# schema4.net
KiCad netlist of a schematic drawn in Altium Designer
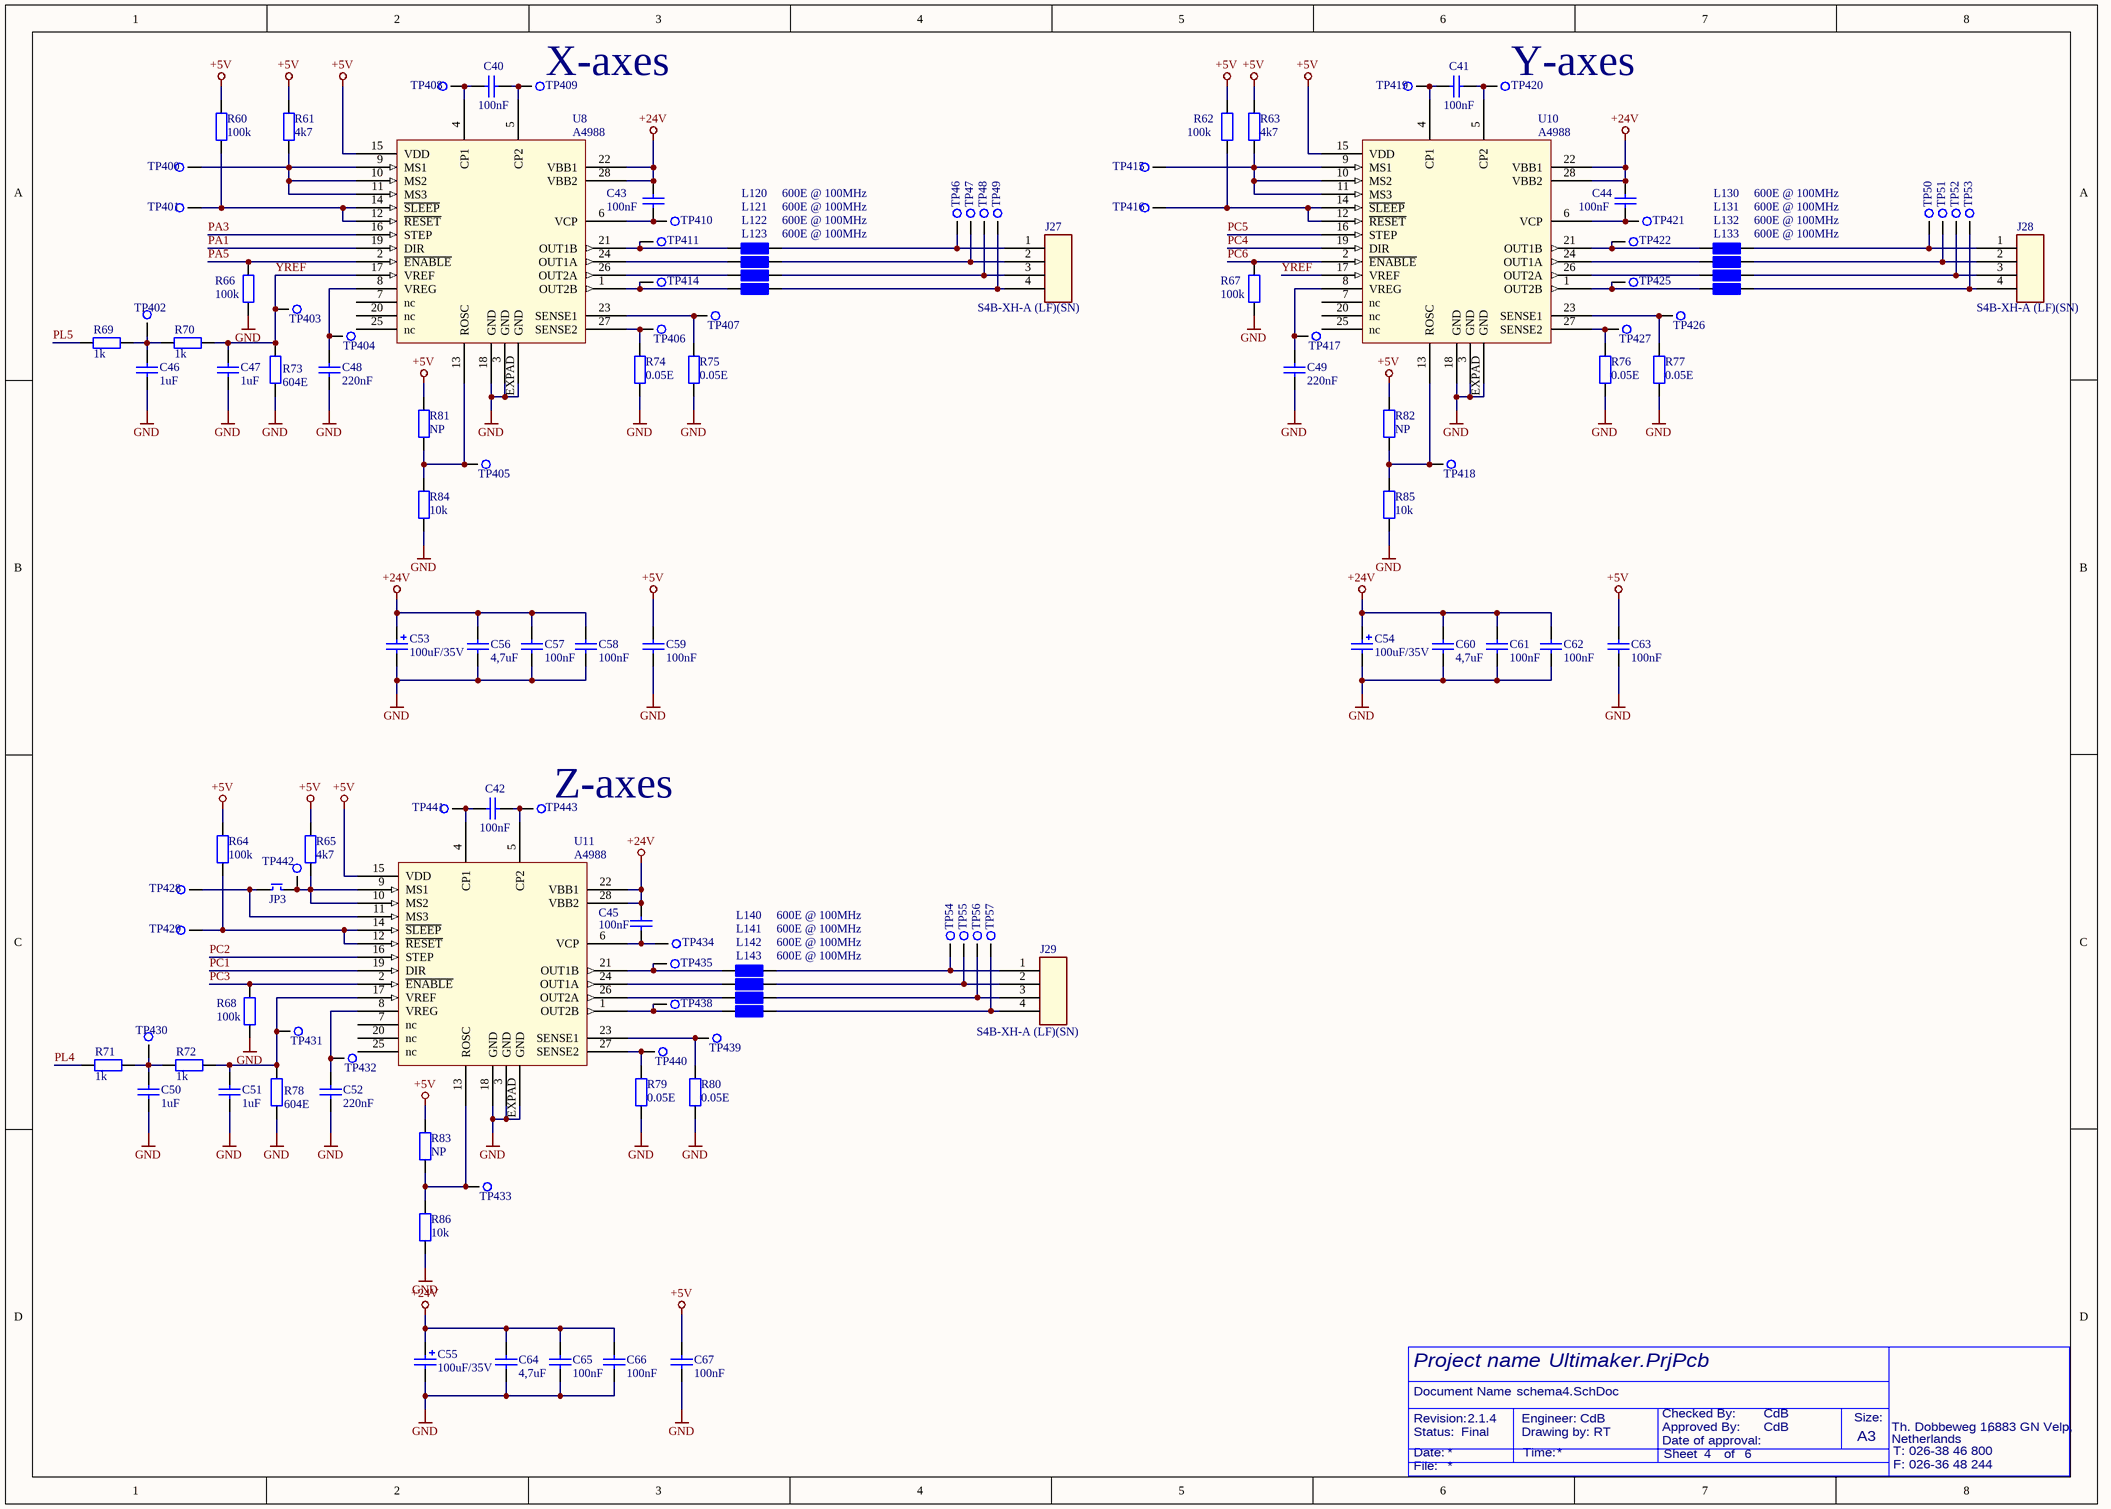
[diagram p0: schema4.SchDoc]

(export (version "E")
  (design (tool "Eeschema 10.0.6"))
  (components
    (comp (ref "C40")
      (value "100nF")
      (footprint "C0603")
      (description "RO X7R 100nF 10% 50V 0603")
      (libsource (lib "Database_Faber") (part "Capacitor"))
    )
    (comp (ref "C41")
      (value "100nF")
      (footprint "C0603")
      (description "RO X7R 100nF 10% 50V 0603")
      (libsource (lib "Database_Faber") (part "Capacitor"))
    )
    (comp (ref "C42")
      (value "100nF")
      (footprint "C0603")
      (description "RO X7R 100nF 10% 50V 0603")
      (libsource (lib "Database_Faber") (part "Capacitor"))
    )
    (comp (ref "C43")
      (value "100nF")
      (footprint "C0603")
      (description "RO X7R 100nF 10% 50V 0603")
      (libsource (lib "Database_Faber") (part "Capacitor"))
    )
    (comp (ref "C44")
      (value "100nF")
      (footprint "C0603")
      (description "RO X7R 100nF 10% 50V 0603")
      (libsource (lib "Database_Faber") (part "Capacitor"))
    )
    (comp (ref "C45")
      (value "100nF")
      (footprint "C0603")
      (description "RO X7R 100nF 10% 50V 0603")
      (libsource (lib "Database_Faber") (part "Capacitor"))
    )
    (comp (ref "C46")
      (value "1uF")
      (footprint "C0603")
      (description "RO X5R 1uF 10% 10V 0603")
      (libsource (lib "Database_Faber") (part "Capacitor"))
    )
    (comp (ref "C47")
      (value "1uF")
      (footprint "C0603")
      (description "RO X5R 1uF 10% 10V 0603")
      (libsource (lib "Database_Faber") (part "Capacitor"))
    )
    (comp (ref "C48")
      (value "220nF")
      (footprint "C0603")
      (description "RO X7R 220nF 10% 25V  0603")
      (libsource (lib "Database_Faber") (part "Capacitor"))
    )
    (comp (ref "C49")
      (value "220nF")
      (footprint "C0603")
      (description "RO X7R 220nF 10% 25V  0603")
      (libsource (lib "Database_Faber") (part "Capacitor"))
    )
    (comp (ref "C50")
      (value "1uF")
      (footprint "C0603")
      (description "RO X5R 1uF 10% 10V 0603")
      (libsource (lib "Database_Faber") (part "Capacitor"))
    )
    (comp (ref "C51")
      (value "1uF")
      (footprint "C0603")
      (description "RO X5R 1uF 10% 10V 0603")
      (libsource (lib "Database_Faber") (part "Capacitor"))
    )
    (comp (ref "C52")
      (value "220nF")
      (footprint "C0603")
      (description "RO X7R 220nF 10% 25V  0603")
      (libsource (lib "Database_Faber") (part "Capacitor"))
    )
    (comp (ref "C53")
      (value "100uF/35V")
      (footprint "ELCO Case D")
      (description "RO ELCO 100uF 20% 35V CASE-D EEEFP PAN")
      (libsource (lib "Database_Faber") (part "Capacitor Polarity"))
    )
    (comp (ref "C54")
      (value "100uF/35V")
      (footprint "ELCO Case D")
      (description "RO ELCO 100uF 20% 35V CASE-D EEEFP PAN")
      (libsource (lib "Database_Faber") (part "Capacitor Polarity"))
    )
    (comp (ref "C55")
      (value "100uF/35V")
      (footprint "ELCO Case D")
      (description "RO ELCO 100uF 20% 35V CASE-D EEEFP PAN")
      (libsource (lib "Database_Faber") (part "Capacitor Polarity"))
    )
    (comp (ref "C56")
      (value "4,7uF")
      (footprint "C1206")
      (description "RO X7R 4,7uF 10% 50V 1206")
      (libsource (lib "Database_Faber") (part "Capacitor"))
    )
    (comp (ref "C57")
      (value "100nF")
      (footprint "C0603")
      (description "RO X7R 100nF 10% 50V 0603")
      (libsource (lib "Database_Faber") (part "Capacitor"))
    )
    (comp (ref "C58")
      (value "100nF")
      (footprint "C0603")
      (description "RO X7R 100nF 10% 50V 0603")
      (libsource (lib "Database_Faber") (part "Capacitor"))
    )
    (comp (ref "C59")
      (value "100nF")
      (footprint "C0603")
      (description "RO X7R 100nF 10% 50V 0603")
      (libsource (lib "Database_Faber") (part "Capacitor"))
    )
    (comp (ref "C60")
      (value "4,7uF")
      (footprint "C1206")
      (description "RO X7R 4,7uF 10% 50V 1206")
      (libsource (lib "Database_Faber") (part "Capacitor"))
    )
    (comp (ref "C61")
      (value "100nF")
      (footprint "C0603")
      (description "RO X7R 100nF 10% 50V 0603")
      (libsource (lib "Database_Faber") (part "Capacitor"))
    )
    (comp (ref "C62")
      (value "100nF")
      (footprint "C0603")
      (description "RO X7R 100nF 10% 50V 0603")
      (libsource (lib "Database_Faber") (part "Capacitor"))
    )
    (comp (ref "C63")
      (value "100nF")
      (footprint "C0603")
      (description "RO X7R 100nF 10% 50V 0603")
      (libsource (lib "Database_Faber") (part "Capacitor"))
    )
    (comp (ref "C64")
      (value "4,7uF")
      (footprint "C1206")
      (description "RO X7R 4,7uF 10% 50V 1206")
      (libsource (lib "Database_Faber") (part "Capacitor"))
    )
    (comp (ref "C65")
      (value "100nF")
      (footprint "C0603")
      (description "RO X7R 100nF 10% 50V 0603")
      (libsource (lib "Database_Faber") (part "Capacitor"))
    )
    (comp (ref "C66")
      (value "100nF")
      (footprint "C0603")
      (description "RO X7R 100nF 10% 50V 0603")
      (libsource (lib "Database_Faber") (part "Capacitor"))
    )
    (comp (ref "C67")
      (value "100nF")
      (footprint "C0603")
      (description "RO X7R 100nF 10% 50V 0603")
      (libsource (lib "Database_Faber") (part "Capacitor"))
    )
    (comp (ref "J27")
      (value "S4B-XH-A (LF)(SN)")
      (footprint "S4B-XH-A (LF)(SN)")
      (description "RO CONN PR 4p HKS S4B-XH-A (LF)(SN) JST")
      (fields (field (name "MFG") "JST (JAPAN SOLDERLESS TERMINALS)"))
      (libsource (lib "Database_Faber") (part "HEADER 4"))
    )
    (comp (ref "J28")
      (value "S4B-XH-A (LF)(SN)")
      (footprint "S4B-XH-A (LF)(SN)")
      (description "RO CONN PR 4p HKS S4B-XH-A (LF)(SN) JST")
      (fields (field (name "MFG") "JST (JAPAN SOLDERLESS TERMINALS)"))
      (libsource (lib "Database_Faber") (part "HEADER 4"))
    )
    (comp (ref "J29")
      (value "S4B-XH-A (LF)(SN)")
      (footprint "S4B-XH-A (LF)(SN)")
      (description "RO CONN PR 4p HKS S4B-XH-A (LF)(SN) JST")
      (fields (field (name "MFG") "JST (JAPAN SOLDERLESS TERMINALS)"))
      (libsource (lib "Database_Faber") (part "HEADER 4"))
    )
    (comp (ref "JP3")
      (value "HEADER 2")
      (footprint "HEADER-1x2P-ST-2.54")
      (description "HEADER-1x2P-ST-2.54")
      (libsource (lib "Database_Faber") (part "JUMPER 2"))
    )
    (comp (ref "L120")
      (value "600E @ 100MHz")
      (footprint "R1206")
      (description "FERRIET 742792118 1206 Wurth Elektronik")
      (fields (field (name "MFG") "Wurth Elektronics"))
      (libsource (lib "Ultimaker") (part "Ferriet Bead 600E"))
    )
    (comp (ref "L121")
      (value "600E @ 100MHz")
      (footprint "R1206")
      (description "FERRIET 742792118 1206 Wurth Elektronik")
      (fields (field (name "MFG") "Wurth Elektronics"))
      (libsource (lib "Ultimaker") (part "Ferriet Bead 600E"))
    )
    (comp (ref "L122")
      (value "600E @ 100MHz")
      (footprint "R1206")
      (description "FERRIET 742792118 1206 Wurth Elektronik")
      (fields (field (name "MFG") "Wurth Elektronics"))
      (libsource (lib "Ultimaker") (part "Ferriet Bead 600E"))
    )
    (comp (ref "L123")
      (value "600E @ 100MHz")
      (footprint "R1206")
      (description "FERRIET 742792118 1206 Wurth Elektronik")
      (fields (field (name "MFG") "Wurth Elektronics"))
      (libsource (lib "Ultimaker") (part "Ferriet Bead 600E"))
    )
    (comp (ref "L130")
      (value "600E @ 100MHz")
      (footprint "R1206")
      (description "FERRIET 742792118 1206 Wurth Elektronik")
      (fields (field (name "MFG") "Wurth Elektronics"))
      (libsource (lib "Ultimaker") (part "Ferriet Bead 600E"))
    )
    (comp (ref "L131")
      (value "600E @ 100MHz")
      (footprint "R1206")
      (description "FERRIET 742792118 1206 Wurth Elektronik")
      (fields (field (name "MFG") "Wurth Elektronics"))
      (libsource (lib "Ultimaker") (part "Ferriet Bead 600E"))
    )
    (comp (ref "L132")
      (value "600E @ 100MHz")
      (footprint "R1206")
      (description "FERRIET 742792118 1206 Wurth Elektronik")
      (fields (field (name "MFG") "Wurth Elektronics"))
      (libsource (lib "Ultimaker") (part "Ferriet Bead 600E"))
    )
    (comp (ref "L133")
      (value "600E @ 100MHz")
      (footprint "R1206")
      (description "FERRIET 742792118 1206 Wurth Elektronik")
      (fields (field (name "MFG") "Wurth Elektronics"))
      (libsource (lib "Ultimaker") (part "Ferriet Bead 600E"))
    )
    (comp (ref "L140")
      (value "600E @ 100MHz")
      (footprint "R1206")
      (description "FERRIET 742792118 1206 Wurth Elektronik")
      (fields (field (name "MFG") "Wurth Elektronics"))
      (libsource (lib "Ultimaker") (part "Ferriet Bead 600E"))
    )
    (comp (ref "L141")
      (value "600E @ 100MHz")
      (footprint "R1206")
      (description "FERRIET 742792118 1206 Wurth Elektronik")
      (fields (field (name "MFG") "Wurth Elektronics"))
      (libsource (lib "Ultimaker") (part "Ferriet Bead 600E"))
    )
    (comp (ref "L142")
      (value "600E @ 100MHz")
      (footprint "R1206")
      (description "FERRIET 742792118 1206 Wurth Elektronik")
      (fields (field (name "MFG") "Wurth Elektronics"))
      (libsource (lib "Ultimaker") (part "Ferriet Bead 600E"))
    )
    (comp (ref "L143")
      (value "600E @ 100MHz")
      (footprint "R1206")
      (description "FERRIET 742792118 1206 Wurth Elektronik")
      (fields (field (name "MFG") "Wurth Elektronics"))
      (libsource (lib "Ultimaker") (part "Ferriet Bead 600E"))
    )
    (comp (ref "R60")
      (value "100k")
      (footprint "R0603")
      (description "RO RES 100k0 1% 0,063W  0603")
      (libsource (lib "Database_Faber") (part "Resistor"))
    )
    (comp (ref "R61")
      (value "4k7")
      (footprint "R0603")
      (description "RO RES 4k70 1% 0,063W  0603")
      (libsource (lib "Database_Faber") (part "Resistor"))
    )
    (comp (ref "R62")
      (value "100k")
      (footprint "R0603")
      (description "RO RES 100k0 1% 0,063W  0603")
      (libsource (lib "Database_Faber") (part "Resistor"))
    )
    (comp (ref "R63")
      (value "4k7")
      (footprint "R0603")
      (description "RO RES 4k70 1% 0,063W  0603")
      (libsource (lib "Database_Faber") (part "Resistor"))
    )
    (comp (ref "R64")
      (value "100k")
      (footprint "R0603")
      (description "RO RES 100k0 1% 0,063W  0603")
      (libsource (lib "Database_Faber") (part "Resistor"))
    )
    (comp (ref "R65")
      (value "4k7")
      (footprint "R0603")
      (description "RO RES 4k70 1% 0,063W  0603")
      (libsource (lib "Database_Faber") (part "Resistor"))
    )
    (comp (ref "R66")
      (value "100k")
      (footprint "R0603")
      (description "RO RES 100k0 1% 0,063W  0603")
      (libsource (lib "") (part "Resistor_1"))
    )
    (comp (ref "R67")
      (value "100k")
      (footprint "R0603")
      (description "RO RES 100k0 1% 0,063W  0603")
      (libsource (lib "") (part "Resistor_1"))
    )
    (comp (ref "R68")
      (value "100k")
      (footprint "R0603")
      (description "RO RES 100k0 1% 0,063W  0603")
      (libsource (lib "") (part "Resistor_1"))
    )
    (comp (ref "R69")
      (value "1k")
      (footprint "R0603")
      (description "RO RES 1k0 1% 0,1W  0603")
      (libsource (lib "") (part "Resistor_2"))
    )
    (comp (ref "R70")
      (value "1k")
      (footprint "R0603")
      (description "RO RES 1k0 1% 0,1W  0603")
      (libsource (lib "") (part "Resistor_2"))
    )
    (comp (ref "R71")
      (value "1k")
      (footprint "R0603")
      (description "RO RES 1k0 1% 0,1W  0603")
      (libsource (lib "") (part "Resistor_2"))
    )
    (comp (ref "R72")
      (value "1k")
      (footprint "R0603")
      (description "RO RES 1k0 1% 0,1W  0603")
      (libsource (lib "") (part "Resistor_2"))
    )
    (comp (ref "R73")
      (value "604E")
      (footprint "R0603")
      (description "RO RES 604E 1% 0,063W 0603")
      (fields (field (name "MFG") "VISHAY DRALORIC"))
      (libsource (lib "Database_Faber") (part "Resistor"))
    )
    (comp (ref "R74")
      (value "0.05E")
      (footprint "R0805")
      (description "RO RES 0E05 1% 0,125W 0805")
      (fields (field (name "MFG") "BOURNS"))
      (libsource (lib "Database_Faber") (part "Resistor"))
    )
    (comp (ref "R75")
      (value "0.05E")
      (footprint "R0805")
      (description "RO RES 0E05 1% 0,125W 0805")
      (fields (field (name "MFG") "BOURNS"))
      (libsource (lib "Database_Faber") (part "Resistor"))
    )
    (comp (ref "R76")
      (value "0.05E")
      (footprint "R0805")
      (description "RO RES 0E05 1% 0,125W 0805")
      (fields (field (name "MFG") "BOURNS"))
      (libsource (lib "Database_Faber") (part "Resistor"))
    )
    (comp (ref "R77")
      (value "0.05E")
      (footprint "R0805")
      (description "RO RES 0E05 1% 0,125W 0805")
      (fields (field (name "MFG") "BOURNS"))
      (libsource (lib "Database_Faber") (part "Resistor"))
    )
    (comp (ref "R78")
      (value "604E")
      (footprint "R0603")
      (description "RO RES 604E 1% 0,063W 0603")
      (fields (field (name "MFG") "VISHAY DRALORIC"))
      (libsource (lib "Database_Faber") (part "Resistor"))
    )
    (comp (ref "R79")
      (value "0.05E")
      (footprint "R0805")
      (description "RO RES 0E05 1% 0,125W 0805")
      (fields (field (name "MFG") "BOURNS"))
      (libsource (lib "Database_Faber") (part "Resistor"))
    )
    (comp (ref "R80")
      (value "0.05E")
      (footprint "R0805")
      (description "RO RES 0E05 1% 0,125W 0805")
      (fields (field (name "MFG") "BOURNS"))
      (libsource (lib "Database_Faber") (part "Resistor"))
    )
    (comp (ref "R81") (value "NP") (footprint "R0603") (libsource (lib "Database_Faber") (part "Resistor")))
    (comp (ref "R82") (value "NP") (footprint "R0603") (libsource (lib "Database_Faber") (part "Resistor")))
    (comp (ref "R83") (value "NP") (footprint "R0603") (libsource (lib "Database_Faber") (part "Resistor")))
    (comp (ref "R84")
      (value "10k")
      (footprint "R0603")
      (description "RO RES 10k0 1% 0,063W  0603")
      (libsource (lib "Database_Faber") (part "Resistor"))
    )
    (comp (ref "R85")
      (value "10k")
      (footprint "R0603")
      (description "RO RES 10k0 1% 0,063W  0603")
      (libsource (lib "Database_Faber") (part "Resistor"))
    )
    (comp (ref "R86")
      (value "10k")
      (footprint "R0603")
      (description "RO RES 10k0 1% 0,063W  0603")
      (libsource (lib "Database_Faber") (part "Resistor"))
    )
    (comp (ref "TP46")
      (value "Testpoint")
      (footprint "Testpoint")
      (libsource (lib "Database_Faber") (part "Testpoint"))
    )
    (comp (ref "TP47")
      (value "Testpoint")
      (footprint "Testpoint")
      (libsource (lib "Database_Faber") (part "Testpoint"))
    )
    (comp (ref "TP48")
      (value "Testpoint")
      (footprint "Testpoint")
      (libsource (lib "Database_Faber") (part "Testpoint"))
    )
    (comp (ref "TP49")
      (value "Testpoint")
      (footprint "Testpoint")
      (libsource (lib "Database_Faber") (part "Testpoint"))
    )
    (comp (ref "TP50")
      (value "Testpoint")
      (footprint "Testpoint")
      (libsource (lib "Database_Faber") (part "Testpoint"))
    )
    (comp (ref "TP51")
      (value "Testpoint")
      (footprint "Testpoint")
      (libsource (lib "Database_Faber") (part "Testpoint"))
    )
    (comp (ref "TP52")
      (value "Testpoint")
      (footprint "Testpoint")
      (libsource (lib "Database_Faber") (part "Testpoint"))
    )
    (comp (ref "TP53")
      (value "Testpoint")
      (footprint "Testpoint")
      (libsource (lib "Database_Faber") (part "Testpoint"))
    )
    (comp (ref "TP54")
      (value "Testpoint")
      (footprint "Testpoint")
      (libsource (lib "Database_Faber") (part "Testpoint"))
    )
    (comp (ref "TP55")
      (value "Testpoint")
      (footprint "Testpoint")
      (libsource (lib "Database_Faber") (part "Testpoint"))
    )
    (comp (ref "TP56")
      (value "Testpoint")
      (footprint "Testpoint")
      (libsource (lib "Database_Faber") (part "Testpoint"))
    )
    (comp (ref "TP57")
      (value "Testpoint")
      (footprint "Testpoint")
      (libsource (lib "Database_Faber") (part "Testpoint"))
    )
    (comp (ref "TP400")
      (value "Testpoint 1mm")
      (footprint "Testpoint 1mm")
      (libsource (lib "Ultimaker") (part "Testpoint 1mm"))
    )
    (comp (ref "TP401")
      (value "Testpoint 1mm")
      (footprint "Testpoint 1mm")
      (libsource (lib "Ultimaker") (part "Testpoint 1mm"))
    )
    (comp (ref "TP402")
      (value "Testpoint 1mm")
      (footprint "Testpoint 1mm")
      (libsource (lib "Ultimaker") (part "Testpoint 1mm"))
    )
    (comp (ref "TP403")
      (value "Testpoint 1mm")
      (footprint "Testpoint 1mm")
      (libsource (lib "Ultimaker") (part "Testpoint 1mm"))
    )
    (comp (ref "TP404")
      (value "Testpoint 1mm")
      (footprint "Testpoint 1mm")
      (libsource (lib "Ultimaker") (part "Testpoint 1mm"))
    )
    (comp (ref "TP405")
      (value "Testpoint 1mm")
      (footprint "Testpoint 1mm")
      (libsource (lib "Ultimaker") (part "Testpoint 1mm"))
    )
    (comp (ref "TP406")
      (value "Testpoint 1mm")
      (footprint "Testpoint 1mm")
      (libsource (lib "Ultimaker") (part "Testpoint 1mm"))
    )
    (comp (ref "TP407")
      (value "Testpoint 1mm")
      (footprint "Testpoint 1mm")
      (libsource (lib "Ultimaker") (part "Testpoint 1mm"))
    )
    (comp (ref "TP408")
      (value "Testpoint 1mm")
      (footprint "Testpoint 1mm")
      (libsource (lib "Ultimaker") (part "Testpoint 1mm"))
    )
    (comp (ref "TP409")
      (value "Testpoint 1mm")
      (footprint "Testpoint 1mm")
      (libsource (lib "Ultimaker") (part "Testpoint 1mm"))
    )
    (comp (ref "TP410")
      (value "Testpoint 1mm")
      (footprint "Testpoint 1mm")
      (libsource (lib "Ultimaker") (part "Testpoint 1mm"))
    )
    (comp (ref "TP411")
      (value "Testpoint 1mm")
      (footprint "Testpoint 1mm")
      (libsource (lib "Ultimaker") (part "Testpoint 1mm"))
    )
    (comp (ref "TP414")
      (value "Testpoint 1mm")
      (footprint "Testpoint 1mm")
      (libsource (lib "Ultimaker") (part "Testpoint 1mm"))
    )
    (comp (ref "TP415")
      (value "Testpoint 1mm")
      (footprint "Testpoint 1mm")
      (libsource (lib "Ultimaker") (part "Testpoint 1mm"))
    )
    (comp (ref "TP416")
      (value "Testpoint 1mm")
      (footprint "Testpoint 1mm")
      (libsource (lib "Ultimaker") (part "Testpoint 1mm"))
    )
    (comp (ref "TP417")
      (value "Testpoint 1mm")
      (footprint "Testpoint 1mm")
      (libsource (lib "Ultimaker") (part "Testpoint 1mm"))
    )
    (comp (ref "TP418")
      (value "Testpoint 1mm")
      (footprint "Testpoint 1mm")
      (libsource (lib "Ultimaker") (part "Testpoint 1mm"))
    )
    (comp (ref "TP419")
      (value "Testpoint 1mm")
      (footprint "Testpoint 1mm")
      (libsource (lib "Ultimaker") (part "Testpoint 1mm"))
    )
    (comp (ref "TP420")
      (value "Testpoint 1mm")
      (footprint "Testpoint 1mm")
      (libsource (lib "Ultimaker") (part "Testpoint 1mm"))
    )
    (comp (ref "TP421")
      (value "Testpoint 1mm")
      (footprint "Testpoint 1mm")
      (libsource (lib "Ultimaker") (part "Testpoint 1mm"))
    )
    (comp (ref "TP422")
      (value "Testpoint 1mm")
      (footprint "Testpoint 1mm")
      (libsource (lib "Ultimaker") (part "Testpoint 1mm"))
    )
    (comp (ref "TP425")
      (value "Testpoint 1mm")
      (footprint "Testpoint 1mm")
      (libsource (lib "Ultimaker") (part "Testpoint 1mm"))
    )
    (comp (ref "TP426")
      (value "Testpoint 1mm")
      (footprint "Testpoint 1mm")
      (libsource (lib "Ultimaker") (part "Testpoint 1mm"))
    )
    (comp (ref "TP427")
      (value "Testpoint 1mm")
      (footprint "Testpoint 1mm")
      (libsource (lib "Ultimaker") (part "Testpoint 1mm"))
    )
    (comp (ref "TP428")
      (value "Testpoint 1mm")
      (footprint "Testpoint 1mm")
      (libsource (lib "Ultimaker") (part "Testpoint 1mm"))
    )
    (comp (ref "TP429")
      (value "Testpoint 1mm")
      (footprint "Testpoint 1mm")
      (libsource (lib "Ultimaker") (part "Testpoint 1mm"))
    )
    (comp (ref "TP430")
      (value "Testpoint 1mm")
      (footprint "Testpoint 1mm")
      (libsource (lib "Ultimaker") (part "Testpoint 1mm"))
    )
    (comp (ref "TP431")
      (value "Testpoint 1mm")
      (footprint "Testpoint 1mm")
      (libsource (lib "Ultimaker") (part "Testpoint 1mm"))
    )
    (comp (ref "TP432")
      (value "Testpoint 1mm")
      (footprint "Testpoint 1mm")
      (libsource (lib "Ultimaker") (part "Testpoint 1mm"))
    )
    (comp (ref "TP433")
      (value "Testpoint 1mm")
      (footprint "Testpoint 1mm")
      (libsource (lib "Ultimaker") (part "Testpoint 1mm"))
    )
    (comp (ref "TP434")
      (value "Testpoint 1mm")
      (footprint "Testpoint 1mm")
      (libsource (lib "Ultimaker") (part "Testpoint 1mm"))
    )
    (comp (ref "TP435")
      (value "Testpoint 1mm")
      (footprint "Testpoint 1mm")
      (libsource (lib "Ultimaker") (part "Testpoint 1mm"))
    )
    (comp (ref "TP438")
      (value "Testpoint 1mm")
      (footprint "Testpoint 1mm")
      (libsource (lib "Ultimaker") (part "Testpoint 1mm"))
    )
    (comp (ref "TP439")
      (value "Testpoint 1mm")
      (footprint "Testpoint 1mm")
      (libsource (lib "Ultimaker") (part "Testpoint 1mm"))
    )
    (comp (ref "TP440")
      (value "Testpoint 1mm")
      (footprint "Testpoint 1mm")
      (libsource (lib "Ultimaker") (part "Testpoint 1mm"))
    )
    (comp (ref "TP441")
      (value "Testpoint 1mm")
      (footprint "Testpoint 1mm")
      (libsource (lib "Ultimaker") (part "Testpoint 1mm"))
    )
    (comp (ref "TP442")
      (value "Testpoint 1mm")
      (footprint "Testpoint 1mm")
      (libsource (lib "Ultimaker") (part "Testpoint 1mm"))
    )
    (comp (ref "TP443")
      (value "Testpoint 1mm")
      (footprint "Testpoint 1mm")
      (libsource (lib "Ultimaker") (part "Testpoint 1mm"))
    )
    (comp (ref "U8")
      (value "A4988")
      (footprint "QFN50P500X500X100-28-EX")
      (description "RO IC A4988 QFN-28 ALLEGRO")
      (fields (field (name "MFG") "Allegro"))
      (libsource (lib "Database_Faber") (part "A4988"))
    )
    (comp (ref "U10")
      (value "A4988")
      (footprint "QFN50P500X500X100-28-EX")
      (description "RO IC A4988 QFN-28 ALLEGRO")
      (fields (field (name "MFG") "Allegro"))
      (libsource (lib "Database_Faber") (part "A4988"))
    )
    (comp (ref "U11")
      (value "A4988")
      (footprint "QFN50P500X500X100-28-EX")
      (description "RO IC A4988 QFN-28 ALLEGRO")
      (fields (field (name "MFG") "Allegro"))
      (libsource (lib "Database_Faber") (part "A4988"))
    )
  )
  (nets
    (net (code "1") (name "+5V") (class "Default")
      (node (ref "C59") (pin "2") (pinfunction "2_2") (pintype "passive"))
      (node (ref "C63") (pin "2") (pinfunction "2_2") (pintype "passive"))
      (node (ref "C67") (pin "2") (pinfunction "2_2") (pintype "passive"))
      (node (ref "R60") (pin "2") (pinfunction "2_2") (pintype "passive"))
      (node (ref "R61") (pin "2") (pinfunction "2_2") (pintype "passive"))
      (node (ref "R62") (pin "2") (pinfunction "2_2") (pintype "passive"))
      (node (ref "R63") (pin "2") (pinfunction "2_2") (pintype "passive"))
      (node (ref "R64") (pin "2") (pinfunction "2_2") (pintype "passive"))
      (node (ref "R65") (pin "2") (pinfunction "2_2") (pintype "passive"))
      (node (ref "R81") (pin "2") (pinfunction "2_2") (pintype "passive"))
      (node (ref "R82") (pin "2") (pinfunction "2_2") (pintype "passive"))
      (node (ref "R83") (pin "2") (pinfunction "2_2") (pintype "passive"))
      (node (ref "U10") (pin "15") (pinfunction "VDD_15") (pintype "power_in"))
      (node (ref "U11") (pin "15") (pinfunction "VDD_15") (pintype "power_in"))
      (node (ref "U8") (pin "15") (pinfunction "VDD_15") (pintype "power_in"))
    )
    (net (code "2") (name "+24V") (class "Default")
      (node (ref "C43") (pin "2") (pinfunction "2_2") (pintype "passive"))
      (node (ref "C44") (pin "2") (pinfunction "2_2") (pintype "passive"))
      (node (ref "C45") (pin "2") (pinfunction "2_2") (pintype "passive"))
      (node (ref "C53") (pin "1") (pinfunction "1_1") (pintype "passive"))
      (node (ref "C54") (pin "1") (pinfunction "1_1") (pintype "passive"))
      (node (ref "C55") (pin "1") (pinfunction "1_1") (pintype "passive"))
      (node (ref "C56") (pin "2") (pinfunction "2_2") (pintype "passive"))
      (node (ref "C57") (pin "2") (pinfunction "2_2") (pintype "passive"))
      (node (ref "C58") (pin "2") (pinfunction "2_2") (pintype "passive"))
      (node (ref "C60") (pin "2") (pinfunction "2_2") (pintype "passive"))
      (node (ref "C61") (pin "2") (pinfunction "2_2") (pintype "passive"))
      (node (ref "C62") (pin "2") (pinfunction "2_2") (pintype "passive"))
      (node (ref "C64") (pin "2") (pinfunction "2_2") (pintype "passive"))
      (node (ref "C65") (pin "2") (pinfunction "2_2") (pintype "passive"))
      (node (ref "C66") (pin "2") (pinfunction "2_2") (pintype "passive"))
      (node (ref "U10") (pin "22") (pinfunction "VBB1_22") (pintype "power_in"))
      (node (ref "U10") (pin "28") (pinfunction "VBB2_28") (pintype "power_in"))
      (node (ref "U11") (pin "22") (pinfunction "VBB1_22") (pintype "power_in"))
      (node (ref "U11") (pin "28") (pinfunction "VBB2_28") (pintype "power_in"))
      (node (ref "U8") (pin "22") (pinfunction "VBB1_22") (pintype "power_in"))
      (node (ref "U8") (pin "28") (pinfunction "VBB2_28") (pintype "power_in"))
    )
    (net (code "3") (name "/PA1") (class "Default")
      (node (ref "U8") (pin "19") (pinfunction "DIR_19") (pintype "input"))
    )
    (net (code "4") (name "/PA3") (class "Default")
      (node (ref "U8") (pin "16") (pinfunction "STEP_16") (pintype "input"))
    )
    (net (code "5") (name "/PA5") (class "Default")
      (node (ref "R66") (pin "1") (pinfunction "1_1") (pintype "passive"))
      (node (ref "U8") (pin "2") (pinfunction "~{ENABLE}_2") (pintype "input"))
    )
    (net (code "6") (name "/PC1") (class "Default")
      (node (ref "U11") (pin "19") (pinfunction "DIR_19") (pintype "input"))
    )
    (net (code "7") (name "/PC2") (class "Default")
      (node (ref "U11") (pin "16") (pinfunction "STEP_16") (pintype "input"))
    )
    (net (code "8") (name "/PC3") (class "Default")
      (node (ref "R68") (pin "1") (pinfunction "1_1") (pintype "passive"))
      (node (ref "U11") (pin "2") (pinfunction "~{ENABLE}_2") (pintype "input"))
    )
    (net (code "9") (name "/PC4") (class "Default")
      (node (ref "U10") (pin "19") (pinfunction "DIR_19") (pintype "input"))
    )
    (net (code "10") (name "/PC5") (class "Default")
      (node (ref "U10") (pin "16") (pinfunction "STEP_16") (pintype "input"))
    )
    (net (code "11") (name "/PC6") (class "Default")
      (node (ref "R67") (pin "1") (pinfunction "1_1") (pintype "passive"))
      (node (ref "U10") (pin "2") (pinfunction "~{ENABLE}_2") (pintype "input"))
    )
    (net (code "12") (name "/PL4") (class "Default")
      (node (ref "R71") (pin "1") (pinfunction "1_1") (pintype "passive"))
    )
    (net (code "13") (name "/PL5") (class "Default")
      (node (ref "R69") (pin "1") (pinfunction "1_1") (pintype "passive"))
    )
    (net (code "14") (name "/YREF") (class "Default")
      (node (ref "C47") (pin "2") (pinfunction "2_2") (pintype "passive"))
      (node (ref "R70") (pin "2") (pinfunction "2_2") (pintype "passive"))
      (node (ref "R73") (pin "2") (pinfunction "2_2") (pintype "passive"))
      (node (ref "TP403") (pin "1") (pinfunction "1_1") (pintype "passive"))
      (node (ref "U10") (pin "17") (pinfunction "VREF_17") (pintype "input"))
      (node (ref "U8") (pin "17") (pinfunction "VREF_17") (pintype "input"))
    )
    (net (code "15") (name "GND") (class "Default")
      (node (ref "C46") (pin "1") (pinfunction "1_1") (pintype "passive"))
      (node (ref "C47") (pin "1") (pinfunction "1_1") (pintype "passive"))
      (node (ref "C48") (pin "1") (pinfunction "1_1") (pintype "passive"))
      (node (ref "C49") (pin "1") (pinfunction "1_1") (pintype "passive"))
      (node (ref "C50") (pin "1") (pinfunction "1_1") (pintype "passive"))
      (node (ref "C51") (pin "1") (pinfunction "1_1") (pintype "passive"))
      (node (ref "C52") (pin "1") (pinfunction "1_1") (pintype "passive"))
      (node (ref "C53") (pin "2") (pinfunction "2_2") (pintype "passive"))
      (node (ref "C54") (pin "2") (pinfunction "2_2") (pintype "passive"))
      (node (ref "C55") (pin "2") (pinfunction "2_2") (pintype "passive"))
      (node (ref "C56") (pin "1") (pinfunction "1_1") (pintype "passive"))
      (node (ref "C57") (pin "1") (pinfunction "1_1") (pintype "passive"))
      (node (ref "C58") (pin "1") (pinfunction "1_1") (pintype "passive"))
      (node (ref "C59") (pin "1") (pinfunction "1_1") (pintype "passive"))
      (node (ref "C60") (pin "1") (pinfunction "1_1") (pintype "passive"))
      (node (ref "C61") (pin "1") (pinfunction "1_1") (pintype "passive"))
      (node (ref "C62") (pin "1") (pinfunction "1_1") (pintype "passive"))
      (node (ref "C63") (pin "1") (pinfunction "1_1") (pintype "passive"))
      (node (ref "C64") (pin "1") (pinfunction "1_1") (pintype "passive"))
      (node (ref "C65") (pin "1") (pinfunction "1_1") (pintype "passive"))
      (node (ref "C66") (pin "1") (pinfunction "1_1") (pintype "passive"))
      (node (ref "C67") (pin "1") (pinfunction "1_1") (pintype "passive"))
      (node (ref "R66") (pin "2") (pinfunction "2_2") (pintype "passive"))
      (node (ref "R67") (pin "2") (pinfunction "2_2") (pintype "passive"))
      (node (ref "R68") (pin "2") (pinfunction "2_2") (pintype "passive"))
      (node (ref "R73") (pin "1") (pinfunction "1_1") (pintype "passive"))
      (node (ref "R74") (pin "1") (pinfunction "1_1") (pintype "passive"))
      (node (ref "R75") (pin "1") (pinfunction "1_1") (pintype "passive"))
      (node (ref "R76") (pin "1") (pinfunction "1_1") (pintype "passive"))
      (node (ref "R77") (pin "1") (pinfunction "1_1") (pintype "passive"))
      (node (ref "R78") (pin "1") (pinfunction "1_1") (pintype "passive"))
      (node (ref "R79") (pin "1") (pinfunction "1_1") (pintype "passive"))
      (node (ref "R80") (pin "1") (pinfunction "1_1") (pintype "passive"))
      (node (ref "R84") (pin "1") (pinfunction "1_1") (pintype "passive"))
      (node (ref "R85") (pin "1") (pinfunction "1_1") (pintype "passive"))
      (node (ref "R86") (pin "1") (pinfunction "1_1") (pintype "passive"))
      (node (ref "U10") (pin "18") (pinfunction "GND_18") (pintype "passive"))
      (node (ref "U10") (pin "3") (pinfunction "GND_3") (pintype "power_in"))
      (node (ref "U10") (pin "EXPAD") (pinfunction "GND_EXPAD") (pintype "power_in"))
      (node (ref "U11") (pin "18") (pinfunction "GND_18") (pintype "passive"))
      (node (ref "U11") (pin "3") (pinfunction "GND_3") (pintype "power_in"))
      (node (ref "U11") (pin "EXPAD") (pinfunction "GND_EXPAD") (pintype "power_in"))
      (node (ref "U8") (pin "18") (pinfunction "GND_18") (pintype "passive"))
      (node (ref "U8") (pin "3") (pinfunction "GND_3") (pintype "power_in"))
      (node (ref "U8") (pin "EXPAD") (pinfunction "GND_EXPAD") (pintype "power_in"))
    )
    (net (code "16") (name "Net-(C46-Pad2)") (class "Default")
      (node (ref "C46") (pin "2") (pinfunction "2_2") (pintype "passive"))
      (node (ref "R69") (pin "2") (pinfunction "2_2") (pintype "passive"))
      (node (ref "R70") (pin "1") (pinfunction "1_1") (pintype "passive"))
      (node (ref "TP402") (pin "1") (pinfunction "1_1") (pintype "passive"))
    )
    (net (code "17") (name "Net-(C50-Pad2)") (class "Default")
      (node (ref "C50") (pin "2") (pinfunction "2_2") (pintype "passive"))
      (node (ref "R71") (pin "2") (pinfunction "2_2") (pintype "passive"))
      (node (ref "R72") (pin "1") (pinfunction "1_1") (pintype "passive"))
      (node (ref "TP430") (pin "1") (pinfunction "1_1") (pintype "passive"))
    )
    (net (code "18") (name "Net-(J27-Pad1)") (class "Default")
      (node (ref "J27") (pin "1") (pinfunction "1_1") (pintype "passive"))
      (node (ref "L120") (pin "2") (pinfunction "2_2") (pintype "passive"))
      (node (ref "TP46") (pin "1") (pinfunction "1_1") (pintype "passive"))
    )
    (net (code "19") (name "Net-(J27-Pad2)") (class "Default")
      (node (ref "J27") (pin "2") (pinfunction "2_2") (pintype "passive"))
      (node (ref "L121") (pin "2") (pinfunction "2_2") (pintype "passive"))
      (node (ref "TP47") (pin "1") (pinfunction "1_1") (pintype "passive"))
    )
    (net (code "20") (name "Net-(J27-Pad3)") (class "Default")
      (node (ref "J27") (pin "3") (pinfunction "3_3") (pintype "passive"))
      (node (ref "L122") (pin "2") (pinfunction "2_2") (pintype "passive"))
      (node (ref "TP48") (pin "1") (pinfunction "1_1") (pintype "passive"))
    )
    (net (code "21") (name "Net-(J27-Pad4)") (class "Default")
      (node (ref "J27") (pin "4") (pinfunction "4_4") (pintype "passive"))
      (node (ref "L123") (pin "2") (pinfunction "2_2") (pintype "passive"))
      (node (ref "TP49") (pin "1") (pinfunction "1_1") (pintype "passive"))
    )
    (net (code "22") (name "Net-(J28-Pad1)") (class "Default")
      (node (ref "J28") (pin "1") (pinfunction "1_1") (pintype "passive"))
      (node (ref "L130") (pin "2") (pinfunction "2_2") (pintype "passive"))
      (node (ref "TP50") (pin "1") (pinfunction "1_1") (pintype "passive"))
    )
    (net (code "23") (name "Net-(J28-Pad2)") (class "Default")
      (node (ref "J28") (pin "2") (pinfunction "2_2") (pintype "passive"))
      (node (ref "L131") (pin "2") (pinfunction "2_2") (pintype "passive"))
      (node (ref "TP51") (pin "1") (pinfunction "1_1") (pintype "passive"))
    )
    (net (code "24") (name "Net-(J28-Pad3)") (class "Default")
      (node (ref "J28") (pin "3") (pinfunction "3_3") (pintype "passive"))
      (node (ref "L132") (pin "2") (pinfunction "2_2") (pintype "passive"))
      (node (ref "TP52") (pin "1") (pinfunction "1_1") (pintype "passive"))
    )
    (net (code "25") (name "Net-(J28-Pad4)") (class "Default")
      (node (ref "J28") (pin "4") (pinfunction "4_4") (pintype "passive"))
      (node (ref "L133") (pin "2") (pinfunction "2_2") (pintype "passive"))
      (node (ref "TP53") (pin "1") (pinfunction "1_1") (pintype "passive"))
    )
    (net (code "26") (name "Net-(J29-Pad1)") (class "Default")
      (node (ref "J29") (pin "1") (pinfunction "1_1") (pintype "passive"))
      (node (ref "L140") (pin "2") (pinfunction "2_2") (pintype "passive"))
      (node (ref "TP54") (pin "1") (pinfunction "1_1") (pintype "passive"))
    )
    (net (code "27") (name "Net-(J29-Pad2)") (class "Default")
      (node (ref "J29") (pin "2") (pinfunction "2_2") (pintype "passive"))
      (node (ref "L141") (pin "2") (pinfunction "2_2") (pintype "passive"))
      (node (ref "TP55") (pin "1") (pinfunction "1_1") (pintype "passive"))
    )
    (net (code "28") (name "Net-(J29-Pad3)") (class "Default")
      (node (ref "J29") (pin "3") (pinfunction "3_3") (pintype "passive"))
      (node (ref "L142") (pin "2") (pinfunction "2_2") (pintype "passive"))
      (node (ref "TP56") (pin "1") (pinfunction "1_1") (pintype "passive"))
    )
    (net (code "29") (name "Net-(J29-Pad4)") (class "Default")
      (node (ref "J29") (pin "4") (pinfunction "4_4") (pintype "passive"))
      (node (ref "L143") (pin "2") (pinfunction "2_2") (pintype "passive"))
      (node (ref "TP57") (pin "1") (pinfunction "1_1") (pintype "passive"))
    )
    (net (code "30") (name "Net-(U8-CP1)") (class "Default")
      (node (ref "C40") (pin "1") (pinfunction "1_1") (pintype "passive"))
      (node (ref "TP408") (pin "1") (pinfunction "1_1") (pintype "passive"))
      (node (ref "U8") (pin "4") (pinfunction "CP1_4") (pintype "passive"))
    )
    (net (code "31") (name "Net-(U8-CP2)") (class "Default")
      (node (ref "C40") (pin "2") (pinfunction "2_2") (pintype "passive"))
      (node (ref "TP409") (pin "1") (pinfunction "1_1") (pintype "passive"))
      (node (ref "U8") (pin "5") (pinfunction "CP2_5") (pintype "passive"))
    )
    (net (code "32") (name "Net-(U8-MS1)") (class "Default")
      (node (ref "R61") (pin "1") (pinfunction "1_1") (pintype "passive"))
      (node (ref "TP400") (pin "1") (pinfunction "1_1") (pintype "passive"))
      (node (ref "U8") (pin "10") (pinfunction "MS2_10") (pintype "input"))
      (node (ref "U8") (pin "11") (pinfunction "MS3_11") (pintype "input"))
      (node (ref "U8") (pin "9") (pinfunction "MS1_9") (pintype "input"))
    )
    (net (code "33") (name "Net-(U8-OUT1A)") (class "Default")
      (node (ref "L121") (pin "1") (pinfunction "1_1") (pintype "passive"))
      (node (ref "U8") (pin "24") (pinfunction "OUT1A_24") (pintype "output"))
    )
    (net (code "34") (name "Net-(U8-OUT1B)") (class "Default")
      (node (ref "L120") (pin "1") (pinfunction "1_1") (pintype "passive"))
      (node (ref "TP411") (pin "1") (pinfunction "1_1") (pintype "passive"))
      (node (ref "U8") (pin "21") (pinfunction "OUT1B_21") (pintype "output"))
    )
    (net (code "35") (name "Net-(U8-OUT2A)") (class "Default")
      (node (ref "L122") (pin "1") (pinfunction "1_1") (pintype "passive"))
      (node (ref "U8") (pin "26") (pinfunction "OUT2A_26") (pintype "output"))
    )
    (net (code "36") (name "Net-(U8-OUT2B)") (class "Default")
      (node (ref "L123") (pin "1") (pinfunction "1_1") (pintype "passive"))
      (node (ref "TP414") (pin "1") (pinfunction "1_1") (pintype "passive"))
      (node (ref "U8") (pin "1") (pinfunction "OUT2B_1") (pintype "output"))
    )
    (net (code "37") (name "Net-(U8-ROSC)") (class "Default")
      (node (ref "R81") (pin "1") (pinfunction "1_1") (pintype "passive"))
      (node (ref "R84") (pin "2") (pinfunction "2_2") (pintype "passive"))
      (node (ref "TP405") (pin "1") (pinfunction "1_1") (pintype "passive"))
      (node (ref "U8") (pin "13") (pinfunction "ROSC_13") (pintype "passive"))
    )
    (net (code "38") (name "Net-(U8-SENSE1)") (class "Default")
      (node (ref "R75") (pin "2") (pinfunction "2_2") (pintype "passive"))
      (node (ref "TP407") (pin "1") (pinfunction "1_1") (pintype "passive"))
      (node (ref "U8") (pin "23") (pinfunction "SENSE1_23") (pintype "passive"))
    )
    (net (code "39") (name "Net-(U8-SENSE2)") (class "Default")
      (node (ref "R74") (pin "2") (pinfunction "2_2") (pintype "passive"))
      (node (ref "TP406") (pin "1") (pinfunction "1_1") (pintype "passive"))
      (node (ref "U8") (pin "27") (pinfunction "SENSE2_27") (pintype "passive"))
    )
    (net (code "40") (name "Net-(U8-VCP)") (class "Default")
      (node (ref "C43") (pin "1") (pinfunction "1_1") (pintype "passive"))
      (node (ref "TP410") (pin "1") (pinfunction "1_1") (pintype "passive"))
      (node (ref "U8") (pin "6") (pinfunction "VCP_6") (pintype "passive"))
    )
    (net (code "41") (name "Net-(U8-VREG)") (class "Default")
      (node (ref "C48") (pin "2") (pinfunction "2_2") (pintype "passive"))
      (node (ref "TP404") (pin "1") (pinfunction "1_1") (pintype "passive"))
      (node (ref "U8") (pin "8") (pinfunction "VREG_8") (pintype "power_in"))
    )
    (net (code "42") (name "Net-(U8-~{RESET})") (class "Default")
      (node (ref "R60") (pin "1") (pinfunction "1_1") (pintype "passive"))
      (node (ref "TP401") (pin "1") (pinfunction "1_1") (pintype "passive"))
      (node (ref "U8") (pin "12") (pinfunction "~{RESET}_12") (pintype "input"))
      (node (ref "U8") (pin "14") (pinfunction "~{SLEEP}_14") (pintype "input"))
    )
    (net (code "43") (name "Net-(U10-CP1)") (class "Default")
      (node (ref "C41") (pin "1") (pinfunction "1_1") (pintype "passive"))
      (node (ref "TP419") (pin "1") (pinfunction "1_1") (pintype "passive"))
      (node (ref "U10") (pin "4") (pinfunction "CP1_4") (pintype "passive"))
    )
    (net (code "44") (name "Net-(U10-CP2)") (class "Default")
      (node (ref "C41") (pin "2") (pinfunction "2_2") (pintype "passive"))
      (node (ref "TP420") (pin "1") (pinfunction "1_1") (pintype "passive"))
      (node (ref "U10") (pin "5") (pinfunction "CP2_5") (pintype "passive"))
    )
    (net (code "45") (name "Net-(U10-MS1)") (class "Default")
      (node (ref "R63") (pin "1") (pinfunction "1_1") (pintype "passive"))
      (node (ref "TP415") (pin "1") (pinfunction "1_1") (pintype "passive"))
      (node (ref "U10") (pin "10") (pinfunction "MS2_10") (pintype "input"))
      (node (ref "U10") (pin "11") (pinfunction "MS3_11") (pintype "input"))
      (node (ref "U10") (pin "9") (pinfunction "MS1_9") (pintype "input"))
    )
    (net (code "46") (name "Net-(U10-OUT1A)") (class "Default")
      (node (ref "L131") (pin "1") (pinfunction "1_1") (pintype "passive"))
      (node (ref "U10") (pin "24") (pinfunction "OUT1A_24") (pintype "output"))
    )
    (net (code "47") (name "Net-(U10-OUT1B)") (class "Default")
      (node (ref "L130") (pin "1") (pinfunction "1_1") (pintype "passive"))
      (node (ref "TP422") (pin "1") (pinfunction "1_1") (pintype "passive"))
      (node (ref "U10") (pin "21") (pinfunction "OUT1B_21") (pintype "output"))
    )
    (net (code "48") (name "Net-(U10-OUT2A)") (class "Default")
      (node (ref "L132") (pin "1") (pinfunction "1_1") (pintype "passive"))
      (node (ref "U10") (pin "26") (pinfunction "OUT2A_26") (pintype "output"))
    )
    (net (code "49") (name "Net-(U10-OUT2B)") (class "Default")
      (node (ref "L133") (pin "1") (pinfunction "1_1") (pintype "passive"))
      (node (ref "TP425") (pin "1") (pinfunction "1_1") (pintype "passive"))
      (node (ref "U10") (pin "1") (pinfunction "OUT2B_1") (pintype "output"))
    )
    (net (code "50") (name "Net-(U10-ROSC)") (class "Default")
      (node (ref "R82") (pin "1") (pinfunction "1_1") (pintype "passive"))
      (node (ref "R85") (pin "2") (pinfunction "2_2") (pintype "passive"))
      (node (ref "TP418") (pin "1") (pinfunction "1_1") (pintype "passive"))
      (node (ref "U10") (pin "13") (pinfunction "ROSC_13") (pintype "passive"))
    )
    (net (code "51") (name "Net-(U10-SENSE1)") (class "Default")
      (node (ref "R77") (pin "2") (pinfunction "2_2") (pintype "passive"))
      (node (ref "TP426") (pin "1") (pinfunction "1_1") (pintype "passive"))
      (node (ref "U10") (pin "23") (pinfunction "SENSE1_23") (pintype "passive"))
    )
    (net (code "52") (name "Net-(U10-SENSE2)") (class "Default")
      (node (ref "R76") (pin "2") (pinfunction "2_2") (pintype "passive"))
      (node (ref "TP427") (pin "1") (pinfunction "1_1") (pintype "passive"))
      (node (ref "U10") (pin "27") (pinfunction "SENSE2_27") (pintype "passive"))
    )
    (net (code "53") (name "Net-(U10-VCP)") (class "Default")
      (node (ref "C44") (pin "1") (pinfunction "1_1") (pintype "passive"))
      (node (ref "TP421") (pin "1") (pinfunction "1_1") (pintype "passive"))
      (node (ref "U10") (pin "6") (pinfunction "VCP_6") (pintype "passive"))
    )
    (net (code "54") (name "Net-(U10-VREG)") (class "Default")
      (node (ref "C49") (pin "2") (pinfunction "2_2") (pintype "passive"))
      (node (ref "TP417") (pin "1") (pinfunction "1_1") (pintype "passive"))
      (node (ref "U10") (pin "8") (pinfunction "VREG_8") (pintype "power_in"))
    )
    (net (code "55") (name "Net-(U10-~{RESET})") (class "Default")
      (node (ref "R62") (pin "1") (pinfunction "1_1") (pintype "passive"))
      (node (ref "TP416") (pin "1") (pinfunction "1_1") (pintype "passive"))
      (node (ref "U10") (pin "12") (pinfunction "~{RESET}_12") (pintype "input"))
      (node (ref "U10") (pin "14") (pinfunction "~{SLEEP}_14") (pintype "input"))
    )
    (net (code "56") (name "Net-(U11-CP1)") (class "Default")
      (node (ref "C42") (pin "1") (pinfunction "1_1") (pintype "passive"))
      (node (ref "TP441") (pin "1") (pinfunction "1_1") (pintype "passive"))
      (node (ref "U11") (pin "4") (pinfunction "CP1_4") (pintype "passive"))
    )
    (net (code "57") (name "Net-(U11-CP2)") (class "Default")
      (node (ref "C42") (pin "2") (pinfunction "2_2") (pintype "passive"))
      (node (ref "TP443") (pin "1") (pinfunction "1_1") (pintype "passive"))
      (node (ref "U11") (pin "5") (pinfunction "CP2_5") (pintype "passive"))
    )
    (net (code "58") (name "Net-(U11-MS1)") (class "Default")
      (node (ref "JP3") (pin "2") (pinfunction "2_2") (pintype "passive"))
      (node (ref "R65") (pin "1") (pinfunction "1_1") (pintype "passive"))
      (node (ref "TP442") (pin "1") (pinfunction "1_1") (pintype "passive"))
      (node (ref "U11") (pin "10") (pinfunction "MS2_10") (pintype "input"))
      (node (ref "U11") (pin "9") (pinfunction "MS1_9") (pintype "input"))
    )
    (net (code "59") (name "Net-(U11-MS3)") (class "Default")
      (node (ref "JP3") (pin "1") (pinfunction "1_1") (pintype "passive"))
      (node (ref "TP428") (pin "1") (pinfunction "1_1") (pintype "passive"))
      (node (ref "U11") (pin "11") (pinfunction "MS3_11") (pintype "input"))
    )
    (net (code "60") (name "Net-(U11-OUT1A)") (class "Default")
      (node (ref "L141") (pin "1") (pinfunction "1_1") (pintype "passive"))
      (node (ref "U11") (pin "24") (pinfunction "OUT1A_24") (pintype "output"))
    )
    (net (code "61") (name "Net-(U11-OUT1B)") (class "Default")
      (node (ref "L140") (pin "1") (pinfunction "1_1") (pintype "passive"))
      (node (ref "TP435") (pin "1") (pinfunction "1_1") (pintype "passive"))
      (node (ref "U11") (pin "21") (pinfunction "OUT1B_21") (pintype "output"))
    )
    (net (code "62") (name "Net-(U11-OUT2A)") (class "Default")
      (node (ref "L142") (pin "1") (pinfunction "1_1") (pintype "passive"))
      (node (ref "U11") (pin "26") (pinfunction "OUT2A_26") (pintype "output"))
    )
    (net (code "63") (name "Net-(U11-OUT2B)") (class "Default")
      (node (ref "L143") (pin "1") (pinfunction "1_1") (pintype "passive"))
      (node (ref "TP438") (pin "1") (pinfunction "1_1") (pintype "passive"))
      (node (ref "U11") (pin "1") (pinfunction "OUT2B_1") (pintype "output"))
    )
    (net (code "64") (name "Net-(U11-ROSC)") (class "Default")
      (node (ref "R83") (pin "1") (pinfunction "1_1") (pintype "passive"))
      (node (ref "R86") (pin "2") (pinfunction "2_2") (pintype "passive"))
      (node (ref "TP433") (pin "1") (pinfunction "1_1") (pintype "passive"))
      (node (ref "U11") (pin "13") (pinfunction "ROSC_13") (pintype "passive"))
    )
    (net (code "65") (name "Net-(U11-SENSE1)") (class "Default")
      (node (ref "R80") (pin "2") (pinfunction "2_2") (pintype "passive"))
      (node (ref "TP439") (pin "1") (pinfunction "1_1") (pintype "passive"))
      (node (ref "U11") (pin "23") (pinfunction "SENSE1_23") (pintype "passive"))
    )
    (net (code "66") (name "Net-(U11-SENSE2)") (class "Default")
      (node (ref "R79") (pin "2") (pinfunction "2_2") (pintype "passive"))
      (node (ref "TP440") (pin "1") (pinfunction "1_1") (pintype "passive"))
      (node (ref "U11") (pin "27") (pinfunction "SENSE2_27") (pintype "passive"))
    )
    (net (code "67") (name "Net-(U11-VCP)") (class "Default")
      (node (ref "C45") (pin "1") (pinfunction "1_1") (pintype "passive"))
      (node (ref "TP434") (pin "1") (pinfunction "1_1") (pintype "passive"))
      (node (ref "U11") (pin "6") (pinfunction "VCP_6") (pintype "passive"))
    )
    (net (code "68") (name "Net-(U11-VREF)") (class "Default")
      (node (ref "C51") (pin "2") (pinfunction "2_2") (pintype "passive"))
      (node (ref "R72") (pin "2") (pinfunction "2_2") (pintype "passive"))
      (node (ref "R78") (pin "2") (pinfunction "2_2") (pintype "passive"))
      (node (ref "TP431") (pin "1") (pinfunction "1_1") (pintype "passive"))
      (node (ref "U11") (pin "17") (pinfunction "VREF_17") (pintype "input"))
    )
    (net (code "69") (name "Net-(U11-VREG)") (class "Default")
      (node (ref "C52") (pin "2") (pinfunction "2_2") (pintype "passive"))
      (node (ref "TP432") (pin "1") (pinfunction "1_1") (pintype "passive"))
      (node (ref "U11") (pin "8") (pinfunction "VREG_8") (pintype "power_in"))
    )
    (net (code "70") (name "Net-(U11-~{RESET})") (class "Default")
      (node (ref "R64") (pin "1") (pinfunction "1_1") (pintype "passive"))
      (node (ref "TP429") (pin "1") (pinfunction "1_1") (pintype "passive"))
      (node (ref "U11") (pin "12") (pinfunction "~{RESET}_12") (pintype "input"))
      (node (ref "U11") (pin "14") (pinfunction "~{SLEEP}_14") (pintype "input"))
    )
    (net (code "71") (name "unconnected-(U8-nc-Pad7)") (class "Default")
      (node (ref "U8") (pin "7") (pinfunction "nc_7") (pintype "passive"))
    )
    (net (code "72") (name "unconnected-(U8-nc-Pad20)") (class "Default")
      (node (ref "U8") (pin "20") (pinfunction "nc_20") (pintype "passive"))
    )
    (net (code "73") (name "unconnected-(U8-nc-Pad25)") (class "Default")
      (node (ref "U8") (pin "25") (pinfunction "nc_25") (pintype "passive"))
    )
    (net (code "74") (name "unconnected-(U10-nc-Pad7)") (class "Default")
      (node (ref "U10") (pin "7") (pinfunction "nc_7") (pintype "passive"))
    )
    (net (code "75") (name "unconnected-(U10-nc-Pad20)") (class "Default")
      (node (ref "U10") (pin "20") (pinfunction "nc_20") (pintype "passive"))
    )
    (net (code "76") (name "unconnected-(U10-nc-Pad25)") (class "Default")
      (node (ref "U10") (pin "25") (pinfunction "nc_25") (pintype "passive"))
    )
    (net (code "77") (name "unconnected-(U11-nc-Pad7)") (class "Default")
      (node (ref "U11") (pin "7") (pinfunction "nc_7") (pintype "passive"))
    )
    (net (code "78") (name "unconnected-(U11-nc-Pad20)") (class "Default")
      (node (ref "U11") (pin "20") (pinfunction "nc_20") (pintype "passive"))
    )
    (net (code "79") (name "unconnected-(U11-nc-Pad25)") (class "Default")
      (node (ref "U11") (pin "25") (pinfunction "nc_25") (pintype "passive"))
    )
  )
)
